# Adafruit_MLX90393_Wide_Range_Magnetomete.net
KiCad netlist of a schematic drawn in EAGLE
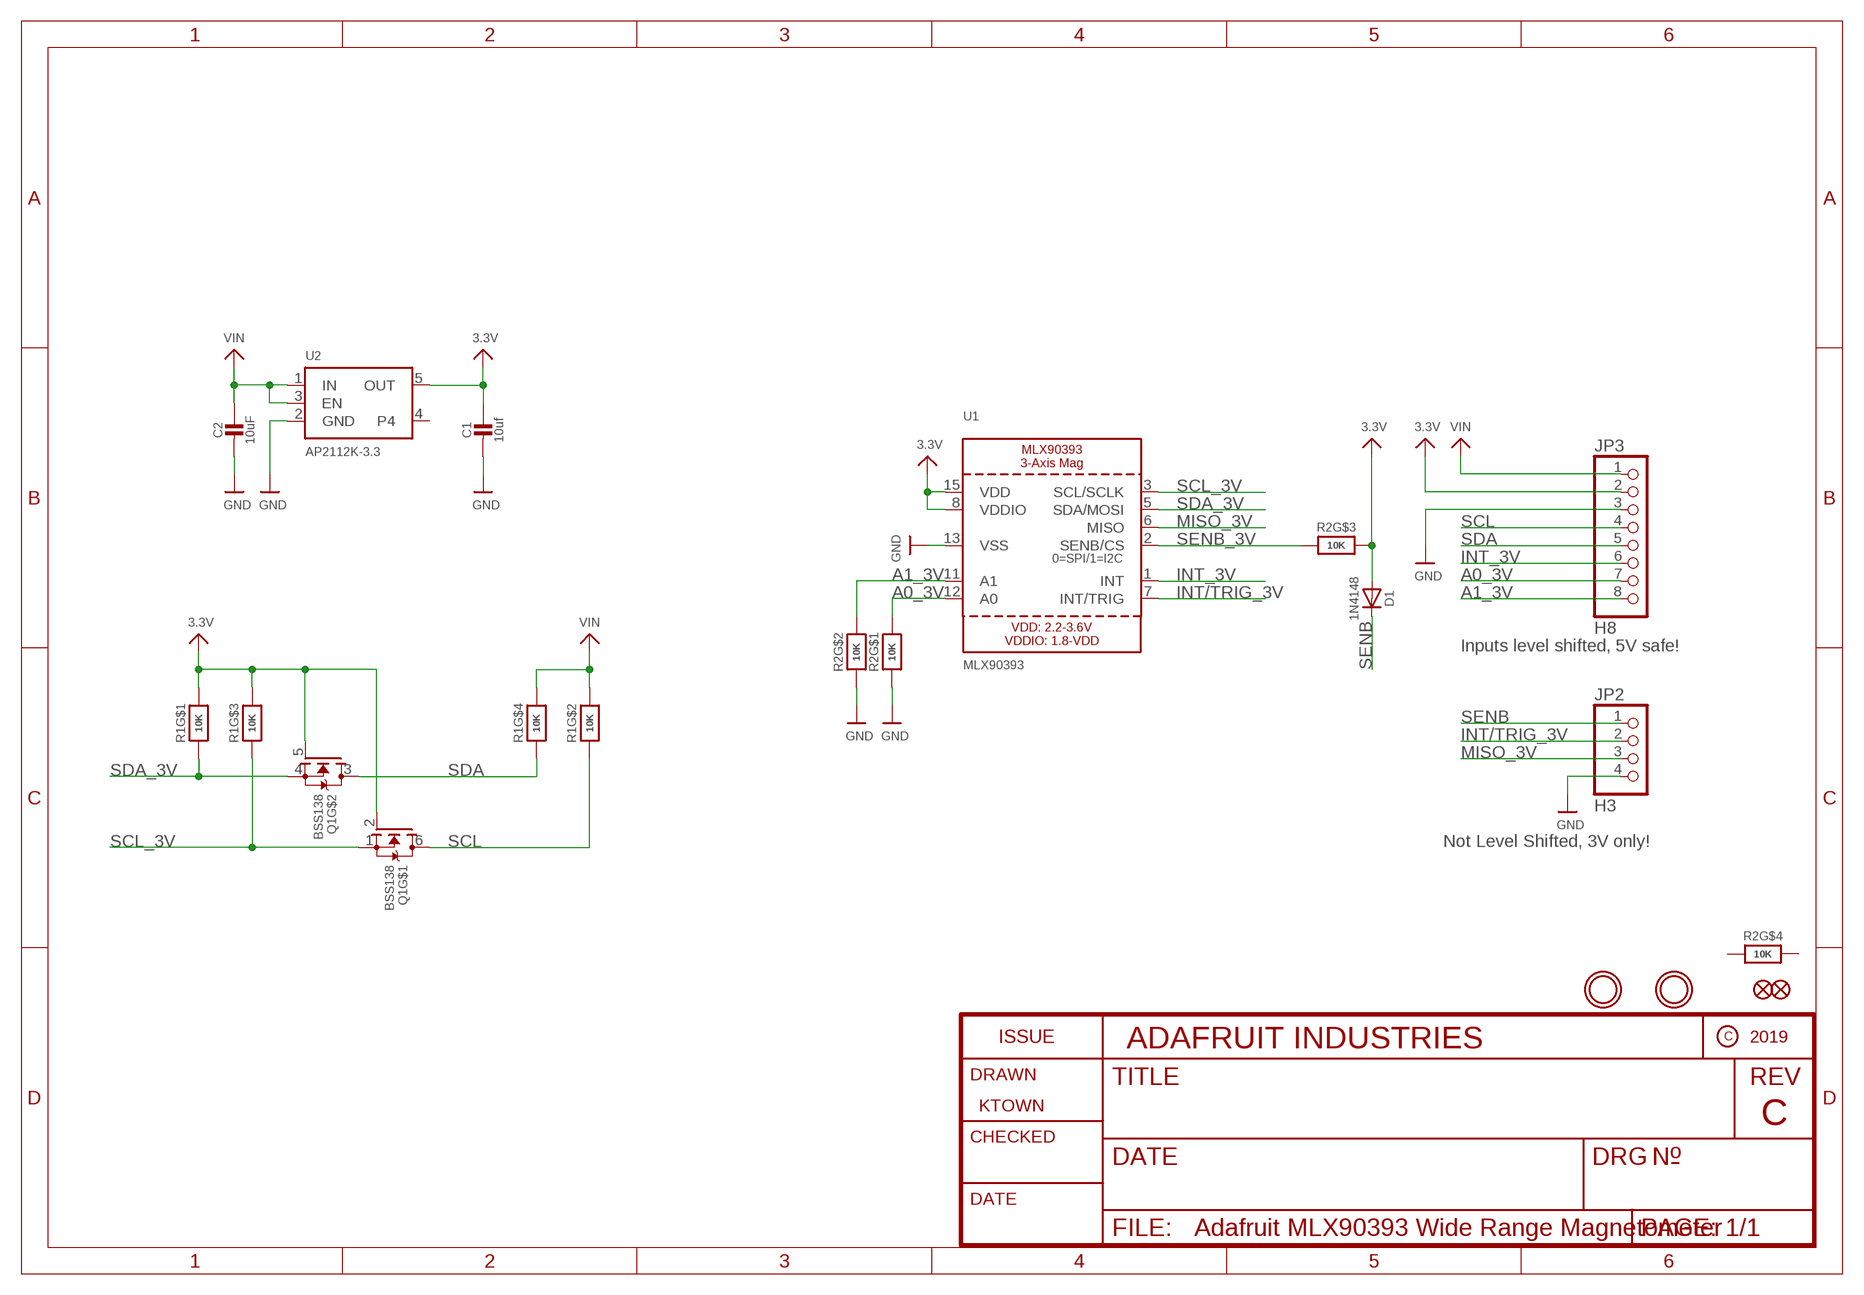
[diagram p0: schematic, sheet 1]

(export (version "E")
  (design (tool "Eeschema 10.0.6"))
  (components
    (comp (ref "C1")
      (value "10uf")
      (footprint "eagle-import:0805_10MGAP")
      (libsource (lib "eagle-import") (part "CAP_CERAMIC0805_10MGAP"))
    )
    (comp (ref "C2")
      (value "10uF")
      (footprint "eagle-import:0805_10MGAP")
      (libsource (lib "eagle-import") (part "CAP_CERAMIC0805_10MGAP"))
    )
    (comp (ref "D1")
      (value "1N4148")
      (footprint "eagle-import:SOD-323")
      (libsource (lib "eagle-import") (part "DIODESOD-323"))
    )
    (comp (ref "FID1")
      (value "FIDUCIAL_1MM")
      (footprint "eagle-import:FIDUCIAL_1MM")
      (libsource (lib "eagle-import") (part "FIDUCIAL_1MM"))
    )
    (comp (ref "FID3")
      (value "FIDUCIAL_1MM")
      (footprint "eagle-import:FIDUCIAL_1MM")
      (libsource (lib "eagle-import") (part "FIDUCIAL_1MM"))
    )
    (comp (ref "JP2")
      (value "H3")
      (footprint "eagle-import:1X04_ROUND")
      (libsource (lib "eagle-import") (part "HEADER-1X4ROUND"))
    )
    (comp (ref "JP3")
      (value "H8")
      (footprint "eagle-import:1X08_ROUND")
      (libsource (lib "eagle-import") (part "HEADER-1X8ROUND"))
    )
    (comp (ref "Q1")
      (value "BSS138")
      (footprint "eagle-import:SOT363")
      (libsource (lib "eagle-import") (part "MOSFET-N_DUAL"))
    )
    (comp (ref "R1")
      (value "10K")
      (footprint "eagle-import:RESPACK_4X0603_NO")
      (libsource (lib "eagle-import") (part "RESISTOR_4PACK_NO"))
    )
    (comp (ref "R2")
      (value "10K")
      (footprint "eagle-import:RESPACK_4X0603_NO")
      (libsource (lib "eagle-import") (part "RESISTOR_4PACK_NO"))
    )
    (comp (ref "U$19")
      (value "MOUNTINGHOLE2.5")
      (footprint "eagle-import:MOUNTINGHOLE_2.5_PLATED")
      (libsource (lib "eagle-import") (part "MOUNTINGHOLE2.5"))
    )
    (comp (ref "U$23")
      (value "MOUNTINGHOLE2.5")
      (footprint "eagle-import:MOUNTINGHOLE_2.5_PLATED")
      (libsource (lib "eagle-import") (part "MOUNTINGHOLE2.5"))
    )
    (comp (ref "U1")
      (value "MLX90393")
      (footprint "eagle-import:QFN16_3MM")
      (libsource (lib "eagle-import") (part "MLX90393"))
    )
    (comp (ref "U2")
      (value "AP2112K-3.3")
      (footprint "eagle-import:SOT23-5")
      (libsource (lib "eagle-import") (part "VREG_SOT23-5"))
    )
  )
  (nets
    (net (code "1") (name "/A0_3V") (class "Default")
      (node (ref "JP3") (pin "7") (pinfunction "7_7") (pintype "passive"))
      (node (ref "R2") (pin "8") (pinfunction "2_8") (pintype "passive"))
      (node (ref "U1") (pin "12") (pinfunction "A0_12") (pintype "input"))
    )
    (net (code "2") (name "/A1_3V") (class "Default")
      (node (ref "JP3") (pin "8") (pinfunction "8_8") (pintype "passive"))
      (node (ref "R2") (pin "7") (pinfunction "2_7") (pintype "passive"))
      (node (ref "U1") (pin "11") (pinfunction "A1_11") (pintype "input"))
    )
    (net (code "3") (name "/INT_3V") (class "Default")
      (node (ref "JP3") (pin "6") (pinfunction "6_6") (pintype "passive"))
      (node (ref "U1") (pin "1") (pinfunction "INT_1") (pintype "output"))
    )
    (net (code "4") (name "/INT{slash}TRIG_3V") (class "Default")
      (node (ref "JP2") (pin "2") (pinfunction "2_2") (pintype "passive"))
      (node (ref "U1") (pin "7") (pinfunction "INT/TRIG_7") (pintype "bidirectional"))
    )
    (net (code "5") (name "/MISO_3V") (class "Default")
      (node (ref "JP2") (pin "3") (pinfunction "3_3") (pintype "passive"))
      (node (ref "U1") (pin "6") (pinfunction "MISO_6") (pintype "output"))
    )
    (net (code "6") (name "/SCL") (class "Default")
      (node (ref "JP3") (pin "4") (pinfunction "4_4") (pintype "passive"))
      (node (ref "Q1") (pin "6") (pinfunction "D_6") (pintype "bidirectional"))
      (node (ref "R1") (pin "2") (pinfunction "1_2") (pintype "passive"))
    )
    (net (code "7") (name "/SCL_3V") (class "Default")
      (node (ref "Q1") (pin "1") (pinfunction "S_1") (pintype "bidirectional"))
      (node (ref "R1") (pin "3") (pinfunction "1_3") (pintype "passive"))
      (node (ref "U1") (pin "3") (pinfunction "SCL/SCLK_3") (pintype "input"))
    )
    (net (code "8") (name "/SDA") (class "Default")
      (node (ref "JP3") (pin "5") (pinfunction "5_5") (pintype "passive"))
      (node (ref "Q1") (pin "3") (pinfunction "D_3") (pintype "bidirectional"))
      (node (ref "R1") (pin "4") (pinfunction "1_4") (pintype "passive"))
    )
    (net (code "9") (name "/SDA_3V") (class "Default")
      (node (ref "Q1") (pin "4") (pinfunction "S_4") (pintype "bidirectional"))
      (node (ref "R1") (pin "1") (pinfunction "1_1") (pintype "passive"))
      (node (ref "U1") (pin "5") (pinfunction "SDA/MOSI_5") (pintype "bidirectional"))
    )
    (net (code "10") (name "/SENB") (class "Default")
      (node (ref "D1") (pin "C") (pinfunction "C_C") (pintype "passive"))
      (node (ref "JP2") (pin "1") (pinfunction "1_1") (pintype "passive"))
    )
    (net (code "11") (name "/SENB_3V") (class "Default")
      (node (ref "R2") (pin "3") (pinfunction "1_3") (pintype "passive"))
      (node (ref "U1") (pin "2") (pinfunction "SENB/CS_2") (pintype "input"))
    )
    (net (code "12") (name "3.3V") (class "Default")
      (node (ref "C1") (pin "1") (pinfunction "1_1") (pintype "passive"))
      (node (ref "D1") (pin "A") (pinfunction "A_A") (pintype "passive"))
      (node (ref "JP3") (pin "2") (pinfunction "2_2") (pintype "passive"))
      (node (ref "Q1") (pin "2") (pinfunction "G_2") (pintype "bidirectional"))
      (node (ref "Q1") (pin "5") (pinfunction "G_5") (pintype "bidirectional"))
      (node (ref "R1") (pin "6") (pinfunction "2_6") (pintype "passive"))
      (node (ref "R1") (pin "8") (pinfunction "2_8") (pintype "passive"))
      (node (ref "R2") (pin "6") (pinfunction "2_6") (pintype "passive"))
      (node (ref "U1") (pin "15") (pinfunction "VDD_15") (pintype "power_in"))
      (node (ref "U1") (pin "8") (pinfunction "VDDIO_8") (pintype "power_in"))
      (node (ref "U2") (pin "5") (pinfunction "OUT_5") (pintype "power_in"))
    )
    (net (code "13") (name "GND") (class "Default")
      (node (ref "C1") (pin "2") (pinfunction "2_2") (pintype "passive"))
      (node (ref "C2") (pin "2") (pinfunction "2_2") (pintype "passive"))
      (node (ref "JP2") (pin "4") (pinfunction "4_4") (pintype "passive"))
      (node (ref "JP3") (pin "3") (pinfunction "3_3") (pintype "passive"))
      (node (ref "R2") (pin "1") (pinfunction "1_1") (pintype "passive"))
      (node (ref "R2") (pin "2") (pinfunction "1_2") (pintype "passive"))
      (node (ref "U1") (pin "13") (pinfunction "VSS_13") (pintype "power_in"))
      (node (ref "U2") (pin "2") (pinfunction "GND_2") (pintype "power_in"))
    )
    (net (code "14") (name "VIN") (class "Default")
      (node (ref "C2") (pin "1") (pinfunction "1_1") (pintype "passive"))
      (node (ref "JP3") (pin "1") (pinfunction "1_1") (pintype "passive"))
      (node (ref "R1") (pin "5") (pinfunction "2_5") (pintype "passive"))
      (node (ref "R1") (pin "7") (pinfunction "2_7") (pintype "passive"))
      (node (ref "U2") (pin "1") (pinfunction "IN_1") (pintype "power_in"))
      (node (ref "U2") (pin "3") (pinfunction "EN_3") (pintype "input"))
    )
    (net (code "15") (name "unconnected-(R2D-1-Pad4)") (class "Default")
      (node (ref "R2") (pin "4") (pinfunction "1_4") (pintype "passive"))
    )
    (net (code "16") (name "unconnected-(R2D-2-Pad5)") (class "Default")
      (node (ref "R2") (pin "5") (pinfunction "2_5") (pintype "passive"))
    )
    (net (code "17") (name "unconnected-(U2-P4-Pad4)") (class "Default")
      (node (ref "U2") (pin "4") (pinfunction "P4_4") (pintype "bidirectional"))
    )
  )
)
